# POWER_SWITCHES.net
KiCad netlist of a schematic drawn in Altium Designer
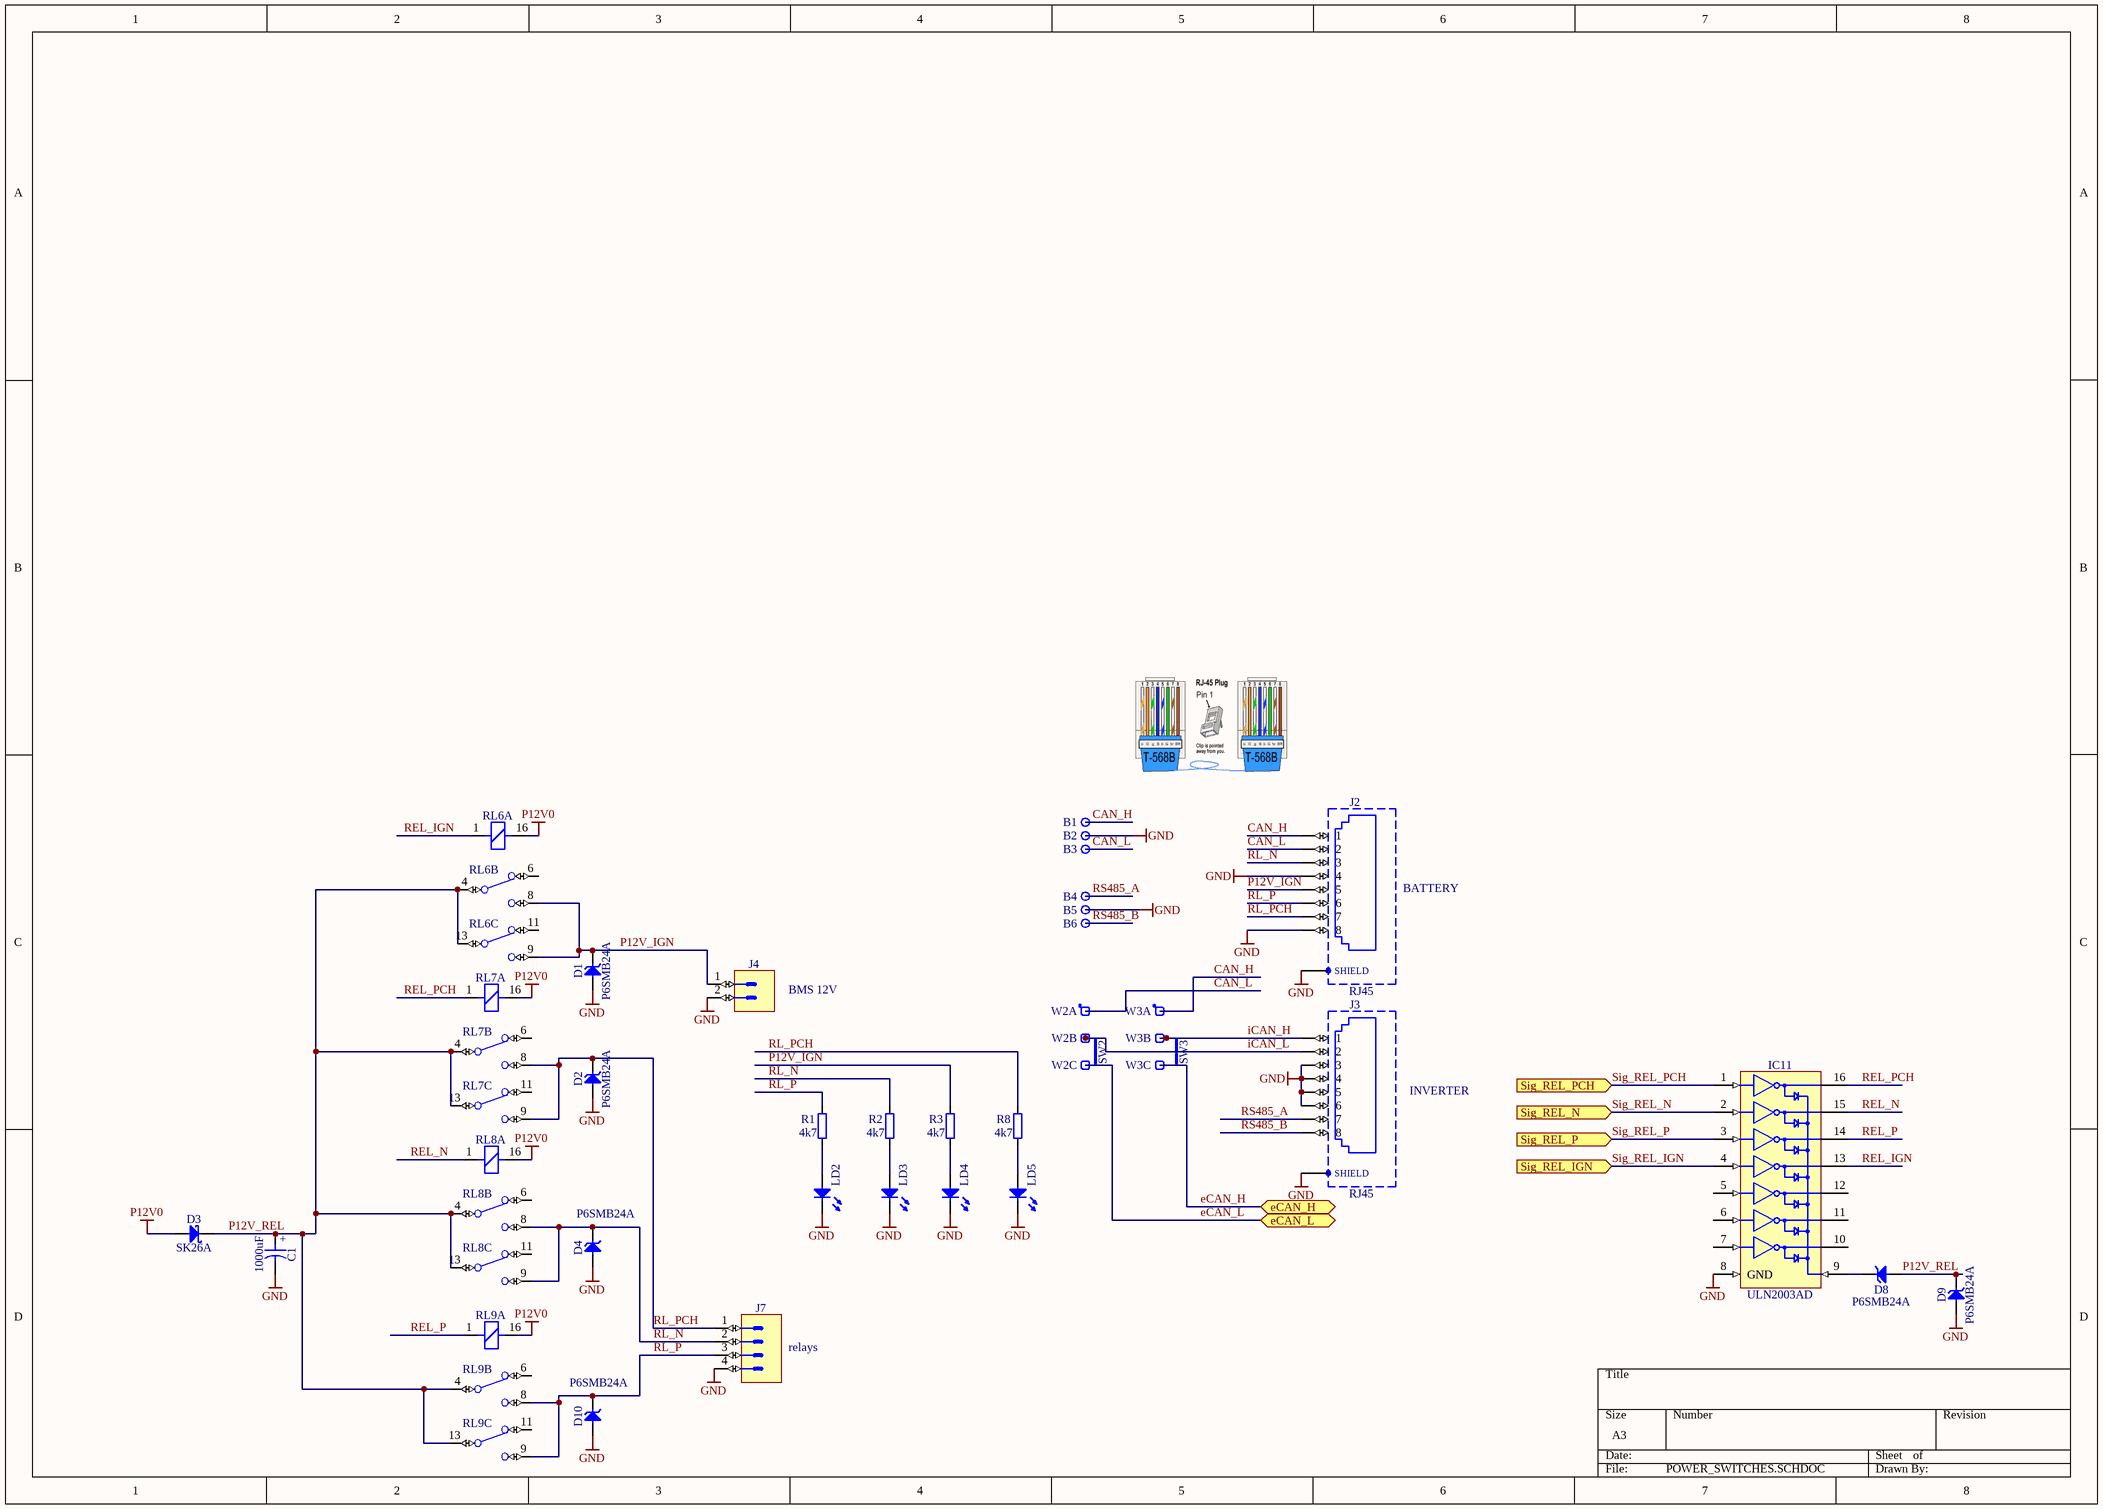
[diagram p0: POWER_SWITCHES.SCHDOC]

(export (version "E")
  (design (tool "Eeschema 10.0.6"))
  (components
    (comp (ref "B1")
      (value "Plated Hole")
      (footprint "c150h80")
      (description "Single Terminal Socket")
      (fields (field (name "PART NUMBER") "PLATED_HOLE0.8_PAD1.5") (field (name "AUTHOR") "CERN DEM JLC"))
      (libsource (lib "Eletro-mechanical") (part "Single Terminal Socket"))
    )
    (comp (ref "B2")
      (value "Plated Hole")
      (footprint "c150h80")
      (description "Single Terminal Socket")
      (fields (field (name "PART NUMBER") "PLATED_HOLE0.8_PAD1.5") (field (name "AUTHOR") "CERN DEM JLC"))
      (libsource (lib "Eletro-mechanical") (part "Single Terminal Socket"))
    )
    (comp (ref "B3")
      (value "Plated Hole")
      (footprint "c150h80")
      (description "Single Terminal Socket")
      (fields (field (name "PART NUMBER") "PLATED_HOLE0.8_PAD1.5") (field (name "AUTHOR") "CERN DEM JLC"))
      (libsource (lib "Eletro-mechanical") (part "Single Terminal Socket"))
    )
    (comp (ref "B4")
      (value "Plated Hole")
      (footprint "c150h80")
      (description "Single Terminal Socket")
      (fields (field (name "PART NUMBER") "PLATED_HOLE0.8_PAD1.5") (field (name "AUTHOR") "CERN DEM JLC"))
      (libsource (lib "Eletro-mechanical") (part "Single Terminal Socket"))
    )
    (comp (ref "B5")
      (value "Plated Hole")
      (footprint "c150h80")
      (description "Single Terminal Socket")
      (fields (field (name "PART NUMBER") "PLATED_HOLE0.8_PAD1.5") (field (name "AUTHOR") "CERN DEM JLC"))
      (libsource (lib "Eletro-mechanical") (part "Single Terminal Socket"))
    )
    (comp (ref "B6")
      (value "Plated Hole")
      (footprint "c150h80")
      (description "Single Terminal Socket")
      (fields (field (name "PART NUMBER") "PLATED_HOLE0.8_PAD1.5") (field (name "AUTHOR") "CERN DEM JLC"))
      (libsource (lib "Eletro-mechanical") (part "Single Terminal Socket"))
    )
    (comp (ref "C1")
      (value "1000uF")
      (footprint "CAPPR500-1050X2200")
      (description "Polarised capacitor")
      (fields
        (field (name "PART NUMBER") "CAER_1000UF_25V_20%_VISHAY_MAL203856102E3")
        (field (name "VOLTAGE") "25V")
        (field (name "AUTHOR") "CERN DEM JLC")
      )
      (libsource (lib "Capacitors") (part "Capacitor - polarized"))
    )
    (comp (ref "D1")
      (value "P6SMB24A")
      (footprint "DIOM5436X261N")
      (description "Transient Voltage Suppressor Diode (Uni-Directional)")
      (fields
        (field (name "VOLTAGE") "24V")
        (field (name "POWER") "600W")
        (field (name "AUTHOR") "CERN DEM JLC")
      )
      (libsource (lib "ICs And Semiconductors") (part "Diode TVS Uni-Directional"))
    )
    (comp (ref "D2")
      (value "P6SMB24A")
      (footprint "DIOM5436X261N")
      (description "Transient Voltage Suppressor Diode (Uni-Directional)")
      (fields
        (field (name "VOLTAGE") "24V")
        (field (name "POWER") "600W")
        (field (name "AUTHOR") "CERN DEM JLC")
      )
      (libsource (lib "ICs And Semiconductors") (part "Diode TVS Uni-Directional"))
    )
    (comp (ref "D3")
      (value "SK26A")
      (footprint "DIOM5126X265N")
      (description "Schottky Diode")
      (fields
        (field (name "VOLTAGE") "60V")
        (field (name "POWER") "2A")
        (field (name "AUTHOR") "CERN DEM JMW")
      )
      (libsource (lib "ICs And Semiconductors") (part "Diode Schottky"))
    )
    (comp (ref "D4")
      (value "P6SMB24A")
      (footprint "DIOM5436X261N")
      (description "Transient Voltage Suppressor Diode (Uni-Directional)")
      (fields
        (field (name "VOLTAGE") "24V")
        (field (name "POWER") "600W")
        (field (name "AUTHOR") "CERN DEM JLC")
      )
      (libsource (lib "ICs And Semiconductors") (part "Diode TVS Uni-Directional"))
    )
    (comp (ref "D8")
      (value "P6SMB24A")
      (footprint "DIOM5436X261N")
      (description "Transient Voltage Suppressor Diode (Uni-Directional)")
      (fields
        (field (name "VOLTAGE") "24V")
        (field (name "POWER") "600W")
        (field (name "AUTHOR") "CERN DEM JLC")
      )
      (libsource (lib "ICs And Semiconductors") (part "Diode TVS Uni-Directional"))
    )
    (comp (ref "D9")
      (value "P6SMB24A")
      (footprint "DIOM5436X261N")
      (description "Transient Voltage Suppressor Diode (Uni-Directional)")
      (fields
        (field (name "VOLTAGE") "24V")
        (field (name "POWER") "600W")
        (field (name "AUTHOR") "CERN DEM JLC")
      )
      (libsource (lib "ICs And Semiconductors") (part "Diode TVS Uni-Directional"))
    )
    (comp (ref "D10")
      (value "P6SMB24A")
      (footprint "DIOM5436X261N")
      (description "Transient Voltage Suppressor Diode (Uni-Directional)")
      (fields
        (field (name "VOLTAGE") "24V")
        (field (name "POWER") "600W")
        (field (name "AUTHOR") "CERN DEM JLC")
      )
      (libsource (lib "ICs And Semiconductors") (part "Diode TVS Uni-Directional"))
    )
    (comp (ref "IC11")
      (value "ULN2003AD")
      (footprint "SOIC127P600X175-16N")
      (description "Seven darlington array")
      (fields (field (name "MANUFACTURER") "TEXAS INSTRUMENTS") (field (name "AUTHOR") "CERN DEM JLC"))
      (libsource (lib "ICs And Semiconductors") (part "ULN2003"))
    )
    (comp (ref "J2")
      (value "RJ45")
      (footprint "HIROSE_TM21R-5C-88")
      (description "Connector RJ45 + Shield")
      (fields
        (field (name "PART NUMBER") "HIROSE_TM21R-5C-88(50)")
        (field (name "MANUFACTURER") "HIROSE (HRS)")
        (field (name "AUTHOR") "CERN DEM BC")
      )
      (libsource (lib "Connectors") (part "Connector RJ45 + Shield"))
    )
    (comp (ref "J3")
      (value "RJ45")
      (footprint "HIROSE_TM21R-5C-88")
      (description "Connector RJ45 + Shield")
      (fields
        (field (name "PART NUMBER") "HIROSE_TM21R-5C-88(50)")
        (field (name "MANUFACTURER") "HIROSE (HRS)")
        (field (name "AUTHOR") "CERN DEM BC")
      )
      (libsource (lib "Connectors") (part "Connector RJ45 + Shield"))
    )
    (comp (ref "J4")
      (value "~")
      (footprint "PHOENIX_1803277")
      (description "Connector 2 Male")
      (fields
        (field (name "PART NUMBER") "PHOENIX_1803277")
        (field (name "MANUFACTURER") "PHOENIX CONTACT")
        (field (name "AUTHOR") "CERN DEM JLC")
      )
      (libsource (lib "Connectors") (part "Connector 2 Male"))
    )
    (comp (ref "J7")
      (value "~")
      (footprint "PHOENIX_1803293")
      (description "Connector 4 Male")
      (fields
        (field (name "PART NUMBER") "PHOENIX_1803293")
        (field (name "MANUFACTURER") "PHOENIX CONTACT")
        (field (name "AUTHOR") "CERN DEM JLC")
      )
      (libsource (lib "Connectors") (part "Connector 4 Male"))
    )
    (comp (ref "LD2")
      (value "Green")
      (footprint "LED_KINGBRIGHT_KP-1608CGCK")
      (description "LED Green 1C 2A")
      (fields
        (field (name "PART NUMBER") "LED_KINGBRIGHT_KP-1608CGCK")
        (field (name "MANUFACTURER") "KINGBRIGHT")
        (field (name "AUTHOR") "CERN DEM HF")
      )
      (libsource (lib "ICs And Semiconductors") (part "LED Green 1C 2A"))
    )
    (comp (ref "LD3")
      (value "Green")
      (footprint "LED_KINGBRIGHT_KP-1608CGCK")
      (description "LED Green 1C 2A")
      (fields
        (field (name "PART NUMBER") "LED_KINGBRIGHT_KP-1608CGCK")
        (field (name "MANUFACTURER") "KINGBRIGHT")
        (field (name "AUTHOR") "CERN DEM HF")
      )
      (libsource (lib "ICs And Semiconductors") (part "LED Green 1C 2A"))
    )
    (comp (ref "LD4")
      (value "Green")
      (footprint "LED_KINGBRIGHT_KP-1608CGCK")
      (description "LED Green 1C 2A")
      (fields
        (field (name "PART NUMBER") "LED_KINGBRIGHT_KP-1608CGCK")
        (field (name "MANUFACTURER") "KINGBRIGHT")
        (field (name "AUTHOR") "CERN DEM HF")
      )
      (libsource (lib "ICs And Semiconductors") (part "LED Green 1C 2A"))
    )
    (comp (ref "LD5")
      (value "Green")
      (footprint "LED_KINGBRIGHT_KP-1608CGCK")
      (description "LED Green 1C 2A")
      (fields
        (field (name "PART NUMBER") "LED_KINGBRIGHT_KP-1608CGCK")
        (field (name "MANUFACTURER") "KINGBRIGHT")
        (field (name "AUTHOR") "CERN DEM HF")
      )
      (libsource (lib "ICs And Semiconductors") (part "LED Green 1C 2A"))
    )
    (comp (ref "R1")
      (value "4k7")
      (footprint "RESC1608X55N")
      (description "Resistor - 1%")
      (fields
        (field (name "PART NUMBER") "R0603_4K7_1%_0.1W_100PPM")
        (field (name "POWER") "0.1W")
        (field (name "AUTHOR") "CERN DEM JLC")
      )
      (libsource (lib "Resistors") (part "Resistor - 1%"))
    )
    (comp (ref "R2")
      (value "4k7")
      (footprint "RESC1608X55N")
      (description "Resistor - 1%")
      (fields
        (field (name "PART NUMBER") "R0603_4K7_1%_0.1W_100PPM")
        (field (name "POWER") "0.1W")
        (field (name "AUTHOR") "CERN DEM JLC")
      )
      (libsource (lib "Resistors") (part "Resistor - 1%"))
    )
    (comp (ref "R3")
      (value "4k7")
      (footprint "RESC1608X55N")
      (description "Resistor - 1%")
      (fields
        (field (name "PART NUMBER") "R0603_4K7_1%_0.1W_100PPM")
        (field (name "POWER") "0.1W")
        (field (name "AUTHOR") "CERN DEM JLC")
      )
      (libsource (lib "Resistors") (part "Resistor - 1%"))
    )
    (comp (ref "R8")
      (value "4k7")
      (footprint "RESC1608X55N")
      (description "Resistor - 1%")
      (fields
        (field (name "PART NUMBER") "R0603_4K7_1%_0.1W_100PPM")
        (field (name "POWER") "0.1W")
        (field (name "AUTHOR") "CERN DEM JLC")
      )
      (libsource (lib "Resistors") (part "Resistor - 1%"))
    )
    (comp (ref "RL6")
      (value "REL_TYCO-AXICOM_MT2")
      (footprint "REL_TYCO-AXICOM_MT2")
      (description "DPDT Signal and RF Relay, MT2 Serie")
      (fields
        (field (name "PART NUMBER") "REL_TYCO-AXICOM_C93402")
        (field (name "MANUFACTURER") "TYCO AXICOM")
        (field (name "AUTHOR") "CERN DEM JLC")
      )
      (libsource (lib "Eletro-mechanical") (part "REL_TYCO-AXICOM_MT2"))
    )
    (comp (ref "RL7")
      (value "REL_TYCO-AXICOM_MT2")
      (footprint "REL_TYCO-AXICOM_MT2")
      (description "DPDT Signal and RF Relay, MT2 Serie")
      (fields
        (field (name "PART NUMBER") "REL_TYCO-AXICOM_C93402")
        (field (name "MANUFACTURER") "TYCO AXICOM")
        (field (name "AUTHOR") "CERN DEM JLC")
      )
      (libsource (lib "Eletro-mechanical") (part "REL_TYCO-AXICOM_MT2"))
    )
    (comp (ref "RL8")
      (value "REL_TYCO-AXICOM_MT2")
      (footprint "REL_TYCO-AXICOM_MT2")
      (description "DPDT Signal and RF Relay, MT2 Serie")
      (fields
        (field (name "PART NUMBER") "REL_TYCO-AXICOM_C93402")
        (field (name "MANUFACTURER") "TYCO AXICOM")
        (field (name "AUTHOR") "CERN DEM JLC")
      )
      (libsource (lib "Eletro-mechanical") (part "REL_TYCO-AXICOM_MT2"))
    )
    (comp (ref "RL9")
      (value "REL_TYCO-AXICOM_MT2")
      (footprint "REL_TYCO-AXICOM_MT2")
      (description "DPDT Signal and RF Relay, MT2 Serie")
      (fields
        (field (name "PART NUMBER") "REL_TYCO-AXICOM_C93402")
        (field (name "MANUFACTURER") "TYCO AXICOM")
        (field (name "AUTHOR") "CERN DEM JLC")
      )
      (libsource (lib "Eletro-mechanical") (part "REL_TYCO-AXICOM_MT2"))
    )
    (comp (ref "SW2")
      (value "Jumper Type1")
      (footprint "JUMPER_BLACK_INSULATED_2.54MM")
      (description "Jumper 1 Pin")
      (fields
        (field (name "PART NUMBER") "COMATEL_313.1730.0.00.40.0")
        (field (name "MANUFACTURER") "KONTEK COMATEL")
        (field (name "AUTHOR") "CERN DEM JLC")
      )
      (libsource (lib "Connectors") (part "Jumper Type1"))
    )
    (comp (ref "SW3")
      (value "Jumper Type1")
      (footprint "JUMPER_BLACK_INSULATED_2.54MM")
      (description "Jumper 1 Pin")
      (fields
        (field (name "PART NUMBER") "COMATEL_313.1730.0.00.40.0")
        (field (name "MANUFACTURER") "KONTEK COMATEL")
        (field (name "AUTHOR") "CERN DEM JLC")
      )
      (libsource (lib "Connectors") (part "Jumper Type1"))
    )
    (comp (ref "W2")
      (value "Test Point")
      (footprint "COMATEL_385.0358.1.03.400")
      (description "3 Mini Wire-Wrap Contact Strip Header")
      (fields
        (field (name "PART NUMBER") "COMATEL_385.0358.1.03.400")
        (field (name "MANUFACTURER") "KONTEK COMATEL")
        (field (name "AUTHOR") "CERN DEM JLC")
      )
      (libsource (lib "Connectors") (part "Wire-Wrap Contact x3"))
    )
    (comp (ref "W3")
      (value "Test Point")
      (footprint "COMATEL_385.0358.1.03.400")
      (description "3 Mini Wire-Wrap Contact Strip Header")
      (fields
        (field (name "PART NUMBER") "COMATEL_385.0358.1.03.400")
        (field (name "MANUFACTURER") "KONTEK COMATEL")
        (field (name "AUTHOR") "CERN DEM JLC")
      )
      (libsource (lib "Connectors") (part "Wire-Wrap Contact x3"))
    )
  )
  (nets
    (net (code "1") (name "/CAN_H") (class "Default")
      (node (ref "B1") (pin "1") (pinfunction "1_1") (pintype "bidirectional"))
      (node (ref "J2") (pin "1") (pinfunction "1_1") (pintype "bidirectional"))
      (node (ref "W3") (pin "1") (pinfunction "1_1") (pintype "bidirectional"))
    )
    (net (code "2") (name "/CAN_L") (class "Default")
      (node (ref "B3") (pin "1") (pinfunction "1_1") (pintype "bidirectional"))
      (node (ref "J2") (pin "2") (pinfunction "2_2") (pintype "bidirectional"))
      (node (ref "W2") (pin "1") (pinfunction "1_1") (pintype "bidirectional"))
    )
    (net (code "3") (name "/P12V_IGN") (class "Default")
      (node (ref "D1") (pin "1") (pinfunction "C_1") (pintype "passive"))
      (node (ref "J2") (pin "5") (pinfunction "5_5") (pintype "bidirectional"))
      (node (ref "J4") (pin "1") (pinfunction "1_1") (pintype "bidirectional"))
      (node (ref "R3") (pin "2") (pinfunction "2_2") (pintype "passive"))
      (node (ref "RL6") (pin "8") (pinfunction "NO_8") (pintype "bidirectional"))
      (node (ref "RL6") (pin "9") (pinfunction "NO_9") (pintype "bidirectional"))
    )
    (net (code "4") (name "/P12V_REL") (class "Default")
      (node (ref "C1") (pin "1") (pinfunction "1_1") (pintype "passive"))
      (node (ref "D3") (pin "1") (pinfunction "C_1") (pintype "passive"))
      (node (ref "D8") (pin "2") (pinfunction "A_2") (pintype "passive"))
      (node (ref "D9") (pin "1") (pinfunction "C_1") (pintype "passive"))
      (node (ref "RL6") (pin "13") (pinfunction "C_13") (pintype "bidirectional"))
      (node (ref "RL6") (pin "4") (pinfunction "C_4") (pintype "bidirectional"))
      (node (ref "RL7") (pin "13") (pinfunction "C_13") (pintype "bidirectional"))
      (node (ref "RL7") (pin "4") (pinfunction "C_4") (pintype "bidirectional"))
      (node (ref "RL8") (pin "13") (pinfunction "C_13") (pintype "bidirectional"))
      (node (ref "RL8") (pin "4") (pinfunction "C_4") (pintype "bidirectional"))
      (node (ref "RL9") (pin "13") (pinfunction "C_13") (pintype "bidirectional"))
      (node (ref "RL9") (pin "4") (pinfunction "C_4") (pintype "bidirectional"))
    )
    (net (code "5") (name "/REL_IGN") (class "Default")
      (node (ref "IC11") (pin "13") (pinfunction "OUT4_13") (pintype "open_collector"))
      (node (ref "RL6") (pin "1") (pinfunction "1_1") (pintype "passive"))
    )
    (net (code "6") (name "/REL_N") (class "Default")
      (node (ref "IC11") (pin "15") (pinfunction "OUT2_15") (pintype "open_collector"))
      (node (ref "RL8") (pin "1") (pinfunction "1_1") (pintype "passive"))
    )
    (net (code "7") (name "/REL_P") (class "Default")
      (node (ref "IC11") (pin "14") (pinfunction "OUT3_14") (pintype "open_collector"))
      (node (ref "RL9") (pin "1") (pinfunction "1_1") (pintype "passive"))
    )
    (net (code "8") (name "/REL_PCH") (class "Default")
      (node (ref "IC11") (pin "16") (pinfunction "OUT1_16") (pintype "open_collector"))
      (node (ref "RL7") (pin "1") (pinfunction "1_1") (pintype "passive"))
    )
    (net (code "9") (name "/RL_N") (class "Default")
      (node (ref "D4") (pin "1") (pinfunction "C_1") (pintype "passive"))
      (node (ref "J2") (pin "3") (pinfunction "3_3") (pintype "bidirectional"))
      (node (ref "J7") (pin "2") (pinfunction "2_2") (pintype "bidirectional"))
      (node (ref "R2") (pin "2") (pinfunction "2_2") (pintype "passive"))
      (node (ref "RL8") (pin "8") (pinfunction "NO_8") (pintype "bidirectional"))
      (node (ref "RL8") (pin "9") (pinfunction "NO_9") (pintype "bidirectional"))
    )
    (net (code "10") (name "/RL_P") (class "Default")
      (node (ref "D10") (pin "1") (pinfunction "C_1") (pintype "passive"))
      (node (ref "J2") (pin "6") (pinfunction "6_6") (pintype "bidirectional"))
      (node (ref "J7") (pin "3") (pinfunction "3_3") (pintype "bidirectional"))
      (node (ref "R1") (pin "2") (pinfunction "2_2") (pintype "passive"))
      (node (ref "RL9") (pin "8") (pinfunction "NO_8") (pintype "bidirectional"))
      (node (ref "RL9") (pin "9") (pinfunction "NO_9") (pintype "bidirectional"))
    )
    (net (code "11") (name "/RL_PCH") (class "Default")
      (node (ref "D2") (pin "1") (pinfunction "C_1") (pintype "passive"))
      (node (ref "J2") (pin "7") (pinfunction "7_7") (pintype "bidirectional"))
      (node (ref "J7") (pin "1") (pinfunction "1_1") (pintype "bidirectional"))
      (node (ref "R8") (pin "2") (pinfunction "2_2") (pintype "passive"))
      (node (ref "RL7") (pin "8") (pinfunction "NO_8") (pintype "bidirectional"))
      (node (ref "RL7") (pin "9") (pinfunction "NO_9") (pintype "bidirectional"))
    )
    (net (code "12") (name "/RS485_A") (class "Default")
      (node (ref "B4") (pin "1") (pinfunction "1_1") (pintype "bidirectional"))
      (node (ref "J3") (pin "7") (pinfunction "7_7") (pintype "bidirectional"))
    )
    (net (code "13") (name "/RS485_B") (class "Default")
      (node (ref "B6") (pin "1") (pinfunction "1_1") (pintype "bidirectional"))
      (node (ref "J3") (pin "8") (pinfunction "8_8") (pintype "bidirectional"))
    )
    (net (code "14") (name "/Sig_REL_IGN") (class "Default")
      (node (ref "IC11") (pin "4") (pinfunction "IN4_4") (pintype "input"))
    )
    (net (code "15") (name "/Sig_REL_N") (class "Default")
      (node (ref "IC11") (pin "2") (pinfunction "IN2_2") (pintype "input"))
    )
    (net (code "16") (name "/Sig_REL_P") (class "Default")
      (node (ref "IC11") (pin "3") (pinfunction "IN3_3") (pintype "input"))
    )
    (net (code "17") (name "/Sig_REL_PCH") (class "Default")
      (node (ref "IC11") (pin "1") (pinfunction "IN1_1") (pintype "input"))
    )
    (net (code "18") (name "/eCAN_H") (class "Default")
      (node (ref "W3") (pin "3") (pinfunction "3_3") (pintype "bidirectional"))
    )
    (net (code "19") (name "/eCAN_L") (class "Default")
      (node (ref "W2") (pin "3") (pinfunction "3_3") (pintype "bidirectional"))
    )
    (net (code "20") (name "/iCAN_H") (class "Default")
      (node (ref "J3") (pin "1") (pinfunction "1_1") (pintype "bidirectional"))
      (node (ref "SW3") (pin "1") (pinfunction "1_1") (pintype "bidirectional"))
      (node (ref "W3") (pin "2") (pinfunction "2_2") (pintype "bidirectional"))
    )
    (net (code "21") (name "/iCAN_L") (class "Default")
      (node (ref "J3") (pin "2") (pinfunction "2_2") (pintype "bidirectional"))
      (node (ref "SW2") (pin "1") (pinfunction "1_1") (pintype "bidirectional"))
      (node (ref "W2") (pin "2") (pinfunction "2_2") (pintype "bidirectional"))
    )
    (net (code "22") (name "GND") (class "Default")
      (node (ref "B2") (pin "1") (pinfunction "1_1") (pintype "bidirectional"))
      (node (ref "B5") (pin "1") (pinfunction "1_1") (pintype "bidirectional"))
      (node (ref "C1") (pin "2") (pinfunction "2_2") (pintype "passive"))
      (node (ref "D1") (pin "2") (pinfunction "A_2") (pintype "passive"))
      (node (ref "D10") (pin "2") (pinfunction "A_2") (pintype "passive"))
      (node (ref "D2") (pin "2") (pinfunction "A_2") (pintype "passive"))
      (node (ref "D4") (pin "2") (pinfunction "A_2") (pintype "passive"))
      (node (ref "D9") (pin "2") (pinfunction "A_2") (pintype "passive"))
      (node (ref "IC11") (pin "8") (pinfunction "GND_8") (pintype "input"))
      (node (ref "J2") (pin "4") (pinfunction "4_4") (pintype "bidirectional"))
      (node (ref "J2") (pin "8") (pinfunction "8_8") (pintype "bidirectional"))
      (node (ref "J2") (pin "SHIELD") (pinfunction "SHIELD_SHIELD") (pintype "passive"))
      (node (ref "J3") (pin "3") (pinfunction "3_3") (pintype "bidirectional"))
      (node (ref "J3") (pin "4") (pinfunction "4_4") (pintype "bidirectional"))
      (node (ref "J3") (pin "5") (pinfunction "5_5") (pintype "bidirectional"))
      (node (ref "J3") (pin "6") (pinfunction "6_6") (pintype "bidirectional"))
      (node (ref "J3") (pin "SHIELD") (pinfunction "SHIELD_SHIELD") (pintype "passive"))
      (node (ref "J4") (pin "2") (pinfunction "2_2") (pintype "bidirectional"))
      (node (ref "J7") (pin "4") (pinfunction "4_4") (pintype "bidirectional"))
      (node (ref "LD2") (pin "1") (pinfunction "C_1") (pintype "passive"))
      (node (ref "LD3") (pin "1") (pinfunction "C_1") (pintype "passive"))
      (node (ref "LD4") (pin "1") (pinfunction "C_1") (pintype "passive"))
      (node (ref "LD5") (pin "1") (pinfunction "C_1") (pintype "passive"))
    )
    (net (code "23") (name "Net-(D8-C)") (class "Default")
      (node (ref "D8") (pin "1") (pinfunction "C_1") (pintype "passive"))
      (node (ref "IC11") (pin "9") (pinfunction "COM_9") (pintype "input"))
    )
    (net (code "24") (name "Net-(LD2-A)") (class "Default")
      (node (ref "LD2") (pin "2") (pinfunction "A_2") (pintype "passive"))
      (node (ref "R1") (pin "1") (pinfunction "1_1") (pintype "passive"))
    )
    (net (code "25") (name "Net-(LD3-A)") (class "Default")
      (node (ref "LD3") (pin "2") (pinfunction "A_2") (pintype "passive"))
      (node (ref "R2") (pin "1") (pinfunction "1_1") (pintype "passive"))
    )
    (net (code "26") (name "Net-(LD4-A)") (class "Default")
      (node (ref "LD4") (pin "2") (pinfunction "A_2") (pintype "passive"))
      (node (ref "R3") (pin "1") (pinfunction "1_1") (pintype "passive"))
    )
    (net (code "27") (name "Net-(LD5-A)") (class "Default")
      (node (ref "LD5") (pin "2") (pinfunction "A_2") (pintype "passive"))
      (node (ref "R8") (pin "1") (pinfunction "1_1") (pintype "passive"))
    )
    (net (code "28") (name "P12V0") (class "Default")
      (node (ref "D3") (pin "2") (pinfunction "A_2") (pintype "passive"))
      (node (ref "RL6") (pin "16") (pinfunction "16_16") (pintype "passive"))
      (node (ref "RL7") (pin "16") (pinfunction "16_16") (pintype "passive"))
      (node (ref "RL8") (pin "16") (pinfunction "16_16") (pintype "passive"))
      (node (ref "RL9") (pin "16") (pinfunction "16_16") (pintype "passive"))
    )
    (net (code "29") (name "unconnected-(IC11-IN5-Pad5)") (class "Default")
      (node (ref "IC11") (pin "5") (pinfunction "IN5_5") (pintype "input"))
    )
    (net (code "30") (name "unconnected-(IC11-IN6-Pad6)") (class "Default")
      (node (ref "IC11") (pin "6") (pinfunction "IN6_6") (pintype "input"))
    )
    (net (code "31") (name "unconnected-(IC11-IN7-Pad7)") (class "Default")
      (node (ref "IC11") (pin "7") (pinfunction "IN7_7") (pintype "input"))
    )
    (net (code "32") (name "unconnected-(IC11-OUT5-Pad12)") (class "Default")
      (node (ref "IC11") (pin "12") (pinfunction "OUT5_12") (pintype "open_collector"))
    )
    (net (code "33") (name "unconnected-(IC11-OUT6-Pad11)") (class "Default")
      (node (ref "IC11") (pin "11") (pinfunction "OUT6_11") (pintype "open_collector"))
    )
    (net (code "34") (name "unconnected-(IC11-OUT7-Pad10)") (class "Default")
      (node (ref "IC11") (pin "10") (pinfunction "OUT7_10") (pintype "open_collector"))
    )
    (net (code "35") (name "unconnected-(RL6B-NC-Pad6)") (class "Default")
      (node (ref "RL6") (pin "6") (pinfunction "NC_6") (pintype "bidirectional"))
    )
    (net (code "36") (name "unconnected-(RL6C-NC-Pad11)") (class "Default")
      (node (ref "RL6") (pin "11") (pinfunction "NC_11") (pintype "bidirectional"))
    )
    (net (code "37") (name "unconnected-(RL7B-NC-Pad6)") (class "Default")
      (node (ref "RL7") (pin "6") (pinfunction "NC_6") (pintype "bidirectional"))
    )
    (net (code "38") (name "unconnected-(RL7C-NC-Pad11)") (class "Default")
      (node (ref "RL7") (pin "11") (pinfunction "NC_11") (pintype "bidirectional"))
    )
    (net (code "39") (name "unconnected-(RL8B-NC-Pad6)") (class "Default")
      (node (ref "RL8") (pin "6") (pinfunction "NC_6") (pintype "bidirectional"))
    )
    (net (code "40") (name "unconnected-(RL8C-NC-Pad11)") (class "Default")
      (node (ref "RL8") (pin "11") (pinfunction "NC_11") (pintype "bidirectional"))
    )
    (net (code "41") (name "unconnected-(RL9B-NC-Pad6)") (class "Default")
      (node (ref "RL9") (pin "6") (pinfunction "NC_6") (pintype "bidirectional"))
    )
    (net (code "42") (name "unconnected-(RL9C-NC-Pad11)") (class "Default")
      (node (ref "RL9") (pin "11") (pinfunction "NC_11") (pintype "bidirectional"))
    )
  )
)
